# RC_Adapter_3.net
KiCad netlist of a schematic drawn in EAGLE
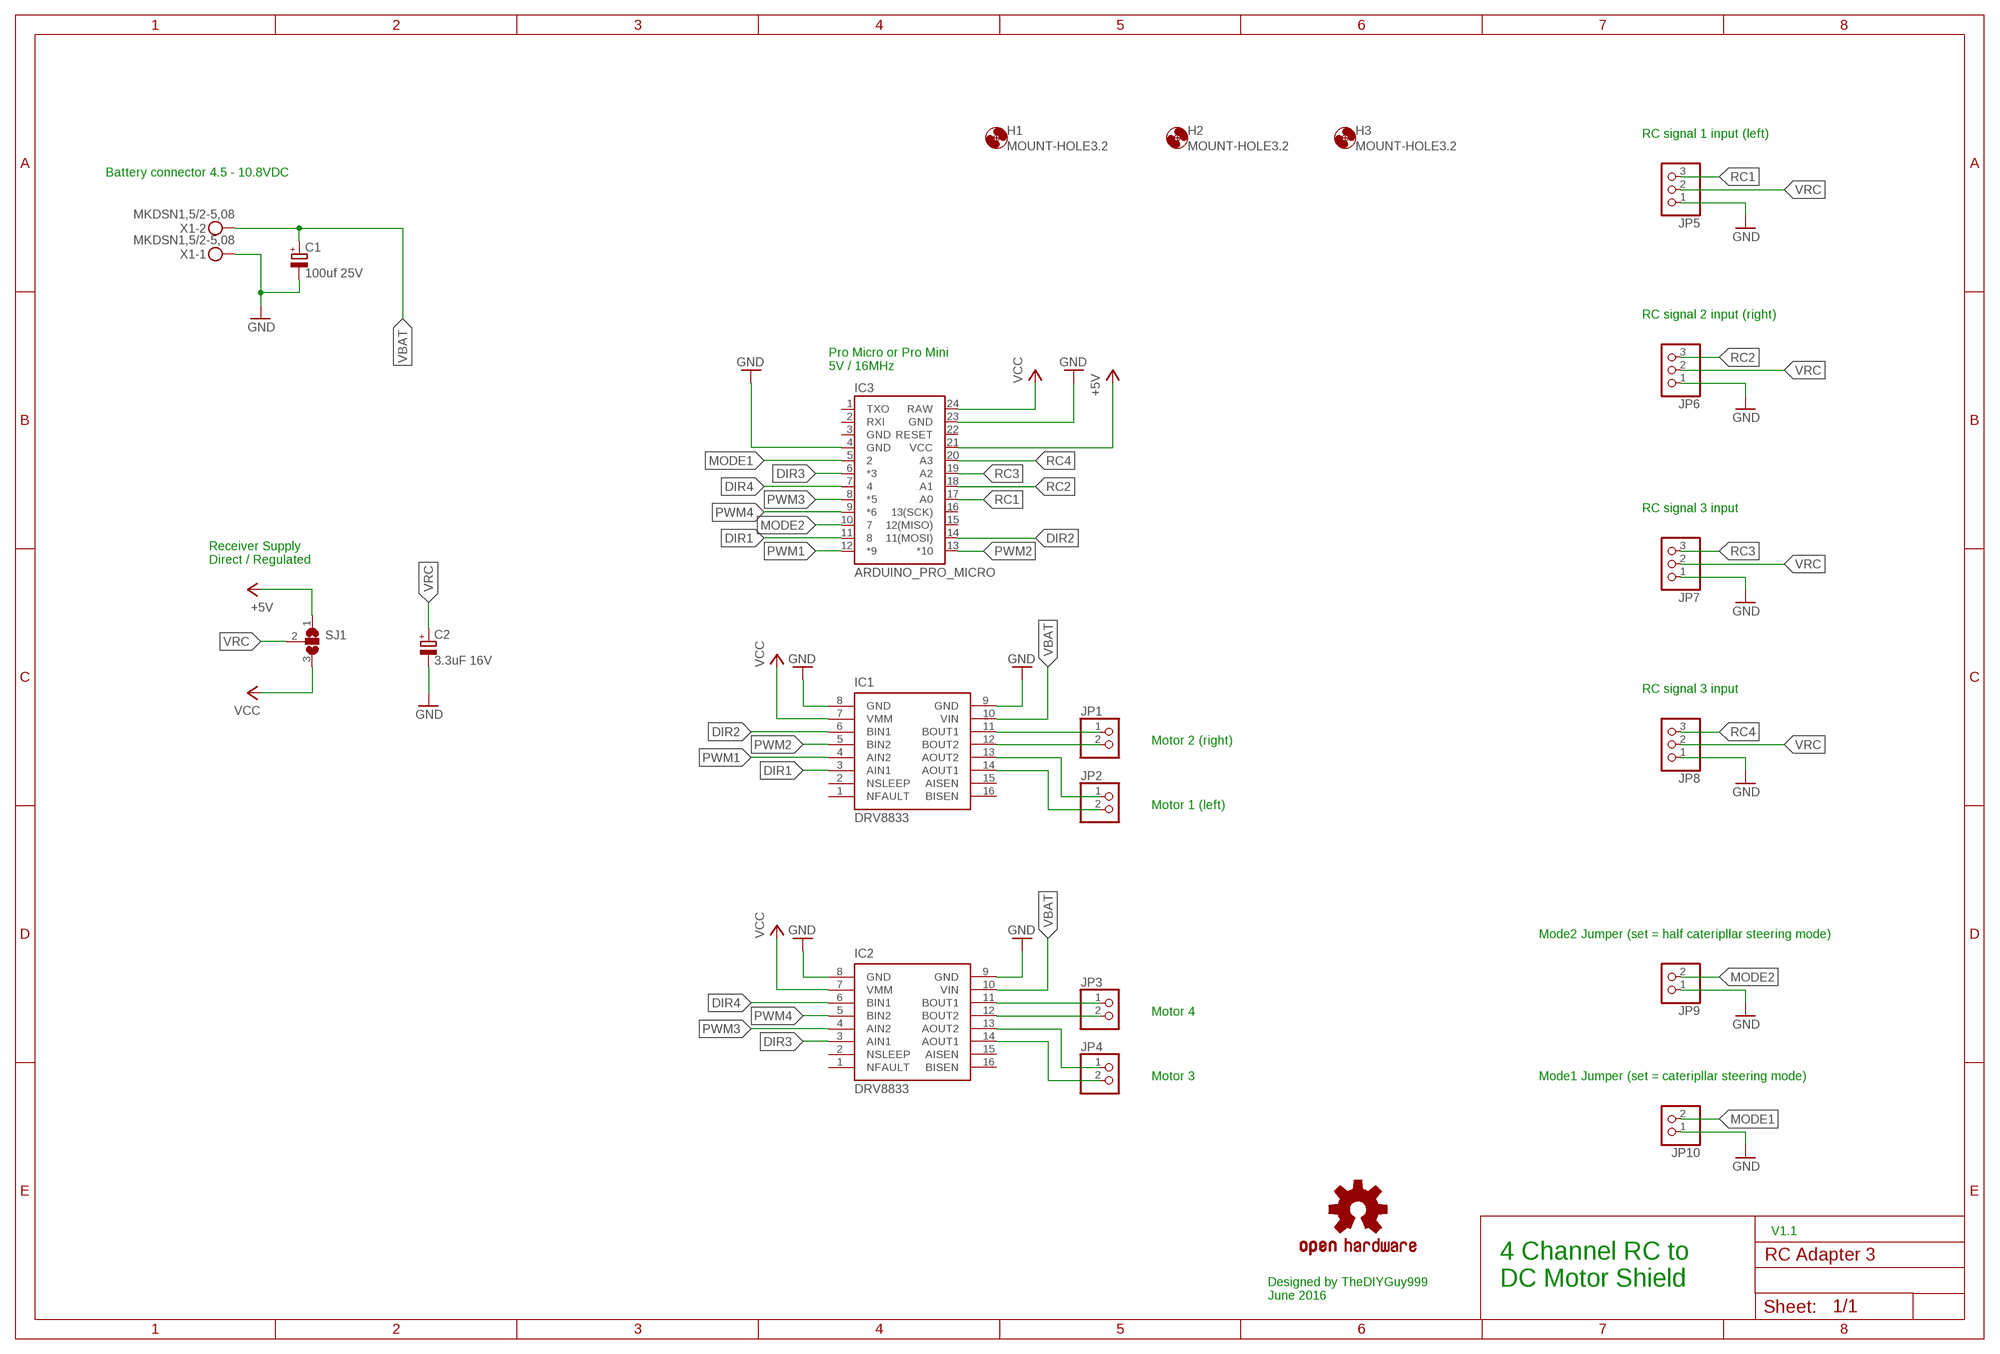
[diagram p0: schematic, sheet 1]

(export (version "E")
  (design (tool "Eeschema 10.0.6"))
  (components
    (comp (ref "C1")
      (value "100uf 25V")
      (footprint "eagle-import:E2,5-6E")
      (libsource (lib "eagle-import") (part "CPOL-EUE2,5-6E"))
    )
    (comp (ref "C2")
      (value "3.3uF 16V")
      (footprint "eagle-import:ETR1")
      (libsource (lib "eagle-import") (part "CPOL-EUETR1"))
    )
    (comp (ref "H1")
      (value "MOUNT-HOLE3.2")
      (footprint "eagle-import:3,2")
      (libsource (lib "eagle-import") (part "MOUNT-HOLE3.2"))
    )
    (comp (ref "H2")
      (value "MOUNT-HOLE3.2")
      (footprint "eagle-import:3,2")
      (libsource (lib "eagle-import") (part "MOUNT-HOLE3.2"))
    )
    (comp (ref "H3")
      (value "MOUNT-HOLE3.2")
      (footprint "eagle-import:3,2")
      (libsource (lib "eagle-import") (part "MOUNT-HOLE3.2"))
    )
    (comp (ref "IC1")
      (value "DRV8833")
      (footprint "eagle-import:DRV8833")
      (libsource (lib "eagle-import") (part "DRV8833"))
    )
    (comp (ref "IC2")
      (value "DRV8833")
      (footprint "eagle-import:DRV8833")
      (libsource (lib "eagle-import") (part "DRV8833"))
    )
    (comp (ref "IC3")
      (value "ARDUINO_PRO_MICRO")
      (footprint "eagle-import:ARDUINO_PRO_MICRO")
      (libsource (lib "eagle-import") (part "ARDUINO_PRO_MICRO"))
    )
    (comp (ref "JP1")
      (value "PINHD-1X2")
      (footprint "eagle-import:1X02")
      (libsource (lib "eagle-import") (part "PINHD-1X2"))
    )
    (comp (ref "JP2")
      (value "PINHD-1X2")
      (footprint "eagle-import:1X02")
      (libsource (lib "eagle-import") (part "PINHD-1X2"))
    )
    (comp (ref "JP3")
      (value "PINHD-1X2")
      (footprint "eagle-import:1X02")
      (libsource (lib "eagle-import") (part "PINHD-1X2"))
    )
    (comp (ref "JP4")
      (value "PINHD-1X2")
      (footprint "eagle-import:1X02")
      (libsource (lib "eagle-import") (part "PINHD-1X2"))
    )
    (comp (ref "JP5")
      (value "PINHD-1X3")
      (footprint "eagle-import:1X03")
      (libsource (lib "eagle-import") (part "PINHD-1X3"))
    )
    (comp (ref "JP6")
      (value "PINHD-1X3")
      (footprint "eagle-import:1X03")
      (libsource (lib "eagle-import") (part "PINHD-1X3"))
    )
    (comp (ref "JP7")
      (value "PINHD-1X3")
      (footprint "eagle-import:1X03")
      (libsource (lib "eagle-import") (part "PINHD-1X3"))
    )
    (comp (ref "JP8")
      (value "PINHD-1X3")
      (footprint "eagle-import:1X03")
      (libsource (lib "eagle-import") (part "PINHD-1X3"))
    )
    (comp (ref "JP9")
      (value "PINHD-1X2")
      (footprint "eagle-import:1X02")
      (libsource (lib "eagle-import") (part "PINHD-1X2"))
    )
    (comp (ref "JP10")
      (value "PINHD-1X2")
      (footprint "eagle-import:1X02")
      (libsource (lib "eagle-import") (part "PINHD-1X2"))
    )
    (comp (ref "LOGO1")
      (value "OSHW-LOGOL")
      (footprint "eagle-import:OSHW-LOGO-L")
      (libsource (lib "eagle-import") (part "OSHW-LOGOL"))
    )
    (comp (ref "SJ1")
      (value "SJ2W")
      (footprint "eagle-import:SJ_2")
      (libsource (lib "eagle-import") (part "SJ2W"))
    )
    (comp (ref "X1")
      (value "MKDSN1,5/2-5,08")
      (footprint "eagle-import:MKDSN1,5_2-5,08")
      (libsource (lib "eagle-import") (part "MKDSN1,5/2-5,08"))
    )
  )
  (nets
    (net (code "1") (name "+5V") (class "Default")
      (node (ref "IC3") (pin "21") (pinfunction "VCC_21") (pintype "bidirectional"))
      (node (ref "SJ1") (pin "1") (pinfunction "1_1") (pintype "passive"))
    )
    (net (code "2") (name "DIR1") (class "Default")
      (node (ref "IC1") (pin "3") (pinfunction "AIN1_3") (pintype "bidirectional"))
      (node (ref "IC3") (pin "11") (pinfunction "8_11") (pintype "bidirectional"))
    )
    (net (code "3") (name "DIR2") (class "Default")
      (node (ref "IC1") (pin "6") (pinfunction "BIN1_6") (pintype "bidirectional"))
      (node (ref "IC3") (pin "14") (pinfunction "11(MOSI)_14") (pintype "bidirectional"))
    )
    (net (code "4") (name "DIR3") (class "Default")
      (node (ref "IC2") (pin "3") (pinfunction "AIN1_3") (pintype "bidirectional"))
      (node (ref "IC3") (pin "6") (pinfunction "*3_6") (pintype "bidirectional"))
    )
    (net (code "5") (name "DIR4") (class "Default")
      (node (ref "IC2") (pin "6") (pinfunction "BIN1_6") (pintype "bidirectional"))
      (node (ref "IC3") (pin "7") (pinfunction "4_7") (pintype "bidirectional"))
    )
    (net (code "6") (name "GND") (class "Default")
      (node (ref "C1") (pin "-") (pinfunction "-_-") (pintype "passive"))
      (node (ref "C2") (pin "-") (pinfunction "-_-") (pintype "passive"))
      (node (ref "IC1") (pin "8") (pinfunction "GND_8") (pintype "bidirectional"))
      (node (ref "IC1") (pin "9") (pinfunction "GND_9") (pintype "bidirectional"))
      (node (ref "IC2") (pin "8") (pinfunction "GND_8") (pintype "bidirectional"))
      (node (ref "IC2") (pin "9") (pinfunction "GND_9") (pintype "bidirectional"))
      (node (ref "IC3") (pin "23") (pinfunction "GND_23") (pintype "bidirectional"))
      (node (ref "IC3") (pin "4") (pinfunction "GND_4") (pintype "bidirectional"))
      (node (ref "JP10") (pin "1") (pinfunction "1_1") (pintype "passive"))
      (node (ref "JP5") (pin "1") (pinfunction "1_1") (pintype "passive"))
      (node (ref "JP6") (pin "1") (pinfunction "1_1") (pintype "passive"))
      (node (ref "JP7") (pin "1") (pinfunction "1_1") (pintype "passive"))
      (node (ref "JP8") (pin "1") (pinfunction "1_1") (pintype "passive"))
      (node (ref "JP9") (pin "1") (pinfunction "1_1") (pintype "passive"))
      (node (ref "X1") (pin "1") (pinfunction "KL_1") (pintype "passive"))
    )
    (net (code "7") (name "MODE1") (class "Default")
      (node (ref "IC3") (pin "5") (pinfunction "2_5") (pintype "bidirectional"))
      (node (ref "JP10") (pin "2") (pinfunction "2_2") (pintype "passive"))
    )
    (net (code "8") (name "MODE2") (class "Default")
      (node (ref "IC3") (pin "10") (pinfunction "7_10") (pintype "bidirectional"))
      (node (ref "JP9") (pin "2") (pinfunction "2_2") (pintype "passive"))
    )
    (net (code "9") (name "Net-(IC1-AOUT1)") (class "Default")
      (node (ref "IC1") (pin "14") (pinfunction "AOUT1_14") (pintype "bidirectional"))
      (node (ref "JP2") (pin "2") (pinfunction "2_2") (pintype "passive"))
    )
    (net (code "10") (name "Net-(IC1-AOUT2)") (class "Default")
      (node (ref "IC1") (pin "13") (pinfunction "AOUT2_13") (pintype "bidirectional"))
      (node (ref "JP2") (pin "1") (pinfunction "1_1") (pintype "passive"))
    )
    (net (code "11") (name "Net-(IC1-BOUT1)") (class "Default")
      (node (ref "IC1") (pin "11") (pinfunction "BOUT1_11") (pintype "bidirectional"))
      (node (ref "JP1") (pin "1") (pinfunction "1_1") (pintype "passive"))
    )
    (net (code "12") (name "Net-(IC1-BOUT2)") (class "Default")
      (node (ref "IC1") (pin "12") (pinfunction "BOUT2_12") (pintype "bidirectional"))
      (node (ref "JP1") (pin "2") (pinfunction "2_2") (pintype "passive"))
    )
    (net (code "13") (name "Net-(IC2-AOUT1)") (class "Default")
      (node (ref "IC2") (pin "14") (pinfunction "AOUT1_14") (pintype "bidirectional"))
      (node (ref "JP4") (pin "2") (pinfunction "2_2") (pintype "passive"))
    )
    (net (code "14") (name "Net-(IC2-AOUT2)") (class "Default")
      (node (ref "IC2") (pin "13") (pinfunction "AOUT2_13") (pintype "bidirectional"))
      (node (ref "JP4") (pin "1") (pinfunction "1_1") (pintype "passive"))
    )
    (net (code "15") (name "Net-(IC2-BOUT1)") (class "Default")
      (node (ref "IC2") (pin "11") (pinfunction "BOUT1_11") (pintype "bidirectional"))
      (node (ref "JP3") (pin "1") (pinfunction "1_1") (pintype "passive"))
    )
    (net (code "16") (name "Net-(IC2-BOUT2)") (class "Default")
      (node (ref "IC2") (pin "12") (pinfunction "BOUT2_12") (pintype "bidirectional"))
      (node (ref "JP3") (pin "2") (pinfunction "2_2") (pintype "passive"))
    )
    (net (code "17") (name "PWM1") (class "Default")
      (node (ref "IC1") (pin "4") (pinfunction "AIN2_4") (pintype "bidirectional"))
      (node (ref "IC3") (pin "12") (pinfunction "*9_12") (pintype "bidirectional"))
    )
    (net (code "18") (name "PWM2") (class "Default")
      (node (ref "IC1") (pin "5") (pinfunction "BIN2_5") (pintype "bidirectional"))
      (node (ref "IC3") (pin "13") (pinfunction "*10_13") (pintype "bidirectional"))
    )
    (net (code "19") (name "PWM3") (class "Default")
      (node (ref "IC2") (pin "4") (pinfunction "AIN2_4") (pintype "bidirectional"))
      (node (ref "IC3") (pin "8") (pinfunction "*5_8") (pintype "bidirectional"))
    )
    (net (code "20") (name "PWM4") (class "Default")
      (node (ref "IC2") (pin "5") (pinfunction "BIN2_5") (pintype "bidirectional"))
      (node (ref "IC3") (pin "9") (pinfunction "*6_9") (pintype "bidirectional"))
    )
    (net (code "21") (name "RC1") (class "Default")
      (node (ref "IC3") (pin "17") (pinfunction "A0_17") (pintype "bidirectional"))
      (node (ref "JP5") (pin "3") (pinfunction "3_3") (pintype "passive"))
    )
    (net (code "22") (name "RC2") (class "Default")
      (node (ref "IC3") (pin "18") (pinfunction "A1_18") (pintype "bidirectional"))
      (node (ref "JP6") (pin "3") (pinfunction "3_3") (pintype "passive"))
    )
    (net (code "23") (name "RC3") (class "Default")
      (node (ref "IC3") (pin "19") (pinfunction "A2_19") (pintype "bidirectional"))
      (node (ref "JP7") (pin "3") (pinfunction "3_3") (pintype "passive"))
    )
    (net (code "24") (name "RC4") (class "Default")
      (node (ref "IC3") (pin "20") (pinfunction "A3_20") (pintype "bidirectional"))
      (node (ref "JP8") (pin "3") (pinfunction "3_3") (pintype "passive"))
    )
    (net (code "25") (name "VBAT") (class "Default")
      (node (ref "C1") (pin "+") (pinfunction "+_+") (pintype "passive"))
      (node (ref "IC1") (pin "10") (pinfunction "VIN_10") (pintype "bidirectional"))
      (node (ref "IC2") (pin "10") (pinfunction "VIN_10") (pintype "bidirectional"))
      (node (ref "X1") (pin "2") (pinfunction "KL_2") (pintype "passive"))
    )
    (net (code "26") (name "VCC") (class "Default")
      (node (ref "IC1") (pin "7") (pinfunction "VMM_7") (pintype "bidirectional"))
      (node (ref "IC2") (pin "7") (pinfunction "VMM_7") (pintype "bidirectional"))
      (node (ref "IC3") (pin "24") (pinfunction "RAW_24") (pintype "bidirectional"))
      (node (ref "SJ1") (pin "3") (pinfunction "3_3") (pintype "passive"))
    )
    (net (code "27") (name "VRC") (class "Default")
      (node (ref "C2") (pin "+") (pinfunction "+_+") (pintype "passive"))
      (node (ref "JP5") (pin "2") (pinfunction "2_2") (pintype "passive"))
      (node (ref "JP6") (pin "2") (pinfunction "2_2") (pintype "passive"))
      (node (ref "JP7") (pin "2") (pinfunction "2_2") (pintype "passive"))
      (node (ref "JP8") (pin "2") (pinfunction "2_2") (pintype "passive"))
      (node (ref "SJ1") (pin "2") (pinfunction "2_2") (pintype "passive"))
    )
    (net (code "28") (name "unconnected-(IC1-AISEN-Pad15)") (class "Default")
      (node (ref "IC1") (pin "15") (pinfunction "AISEN_15") (pintype "bidirectional"))
    )
    (net (code "29") (name "unconnected-(IC1-BISEN-Pad16)") (class "Default")
      (node (ref "IC1") (pin "16") (pinfunction "BISEN_16") (pintype "bidirectional"))
    )
    (net (code "30") (name "unconnected-(IC1-NFAULT-Pad1)") (class "Default")
      (node (ref "IC1") (pin "1") (pinfunction "NFAULT_1") (pintype "bidirectional"))
    )
    (net (code "31") (name "unconnected-(IC1-NSLEEP-Pad2)") (class "Default")
      (node (ref "IC1") (pin "2") (pinfunction "NSLEEP_2") (pintype "bidirectional"))
    )
    (net (code "32") (name "unconnected-(IC2-AISEN-Pad15)") (class "Default")
      (node (ref "IC2") (pin "15") (pinfunction "AISEN_15") (pintype "bidirectional"))
    )
    (net (code "33") (name "unconnected-(IC2-BISEN-Pad16)") (class "Default")
      (node (ref "IC2") (pin "16") (pinfunction "BISEN_16") (pintype "bidirectional"))
    )
    (net (code "34") (name "unconnected-(IC2-NFAULT-Pad1)") (class "Default")
      (node (ref "IC2") (pin "1") (pinfunction "NFAULT_1") (pintype "bidirectional"))
    )
    (net (code "35") (name "unconnected-(IC2-NSLEEP-Pad2)") (class "Default")
      (node (ref "IC2") (pin "2") (pinfunction "NSLEEP_2") (pintype "bidirectional"))
    )
    (net (code "36") (name "unconnected-(IC3-12(MISO)-Pad15)") (class "Default")
      (node (ref "IC3") (pin "15") (pinfunction "12(MISO)_15") (pintype "bidirectional"))
    )
    (net (code "37") (name "unconnected-(IC3-13(SCK)-Pad16)") (class "Default")
      (node (ref "IC3") (pin "16") (pinfunction "13(SCK)_16") (pintype "bidirectional"))
    )
    (net (code "38") (name "unconnected-(IC3-GND-Pad3)") (class "Default")
      (node (ref "IC3") (pin "3") (pinfunction "GND_3") (pintype "bidirectional"))
    )
    (net (code "39") (name "unconnected-(IC3-RESET-Pad22)") (class "Default")
      (node (ref "IC3") (pin "22") (pinfunction "RESET_22") (pintype "bidirectional"))
    )
    (net (code "40") (name "unconnected-(IC3-RXI-Pad2)") (class "Default")
      (node (ref "IC3") (pin "2") (pinfunction "RXI_2") (pintype "bidirectional"))
    )
    (net (code "41") (name "unconnected-(IC3-TXO-Pad1)") (class "Default")
      (node (ref "IC3") (pin "1") (pinfunction "TXO_1") (pintype "bidirectional"))
    )
  )
)
